# PROC099A_Tempsensor.net
KiCad netlist of a schematic drawn in Altium Designer
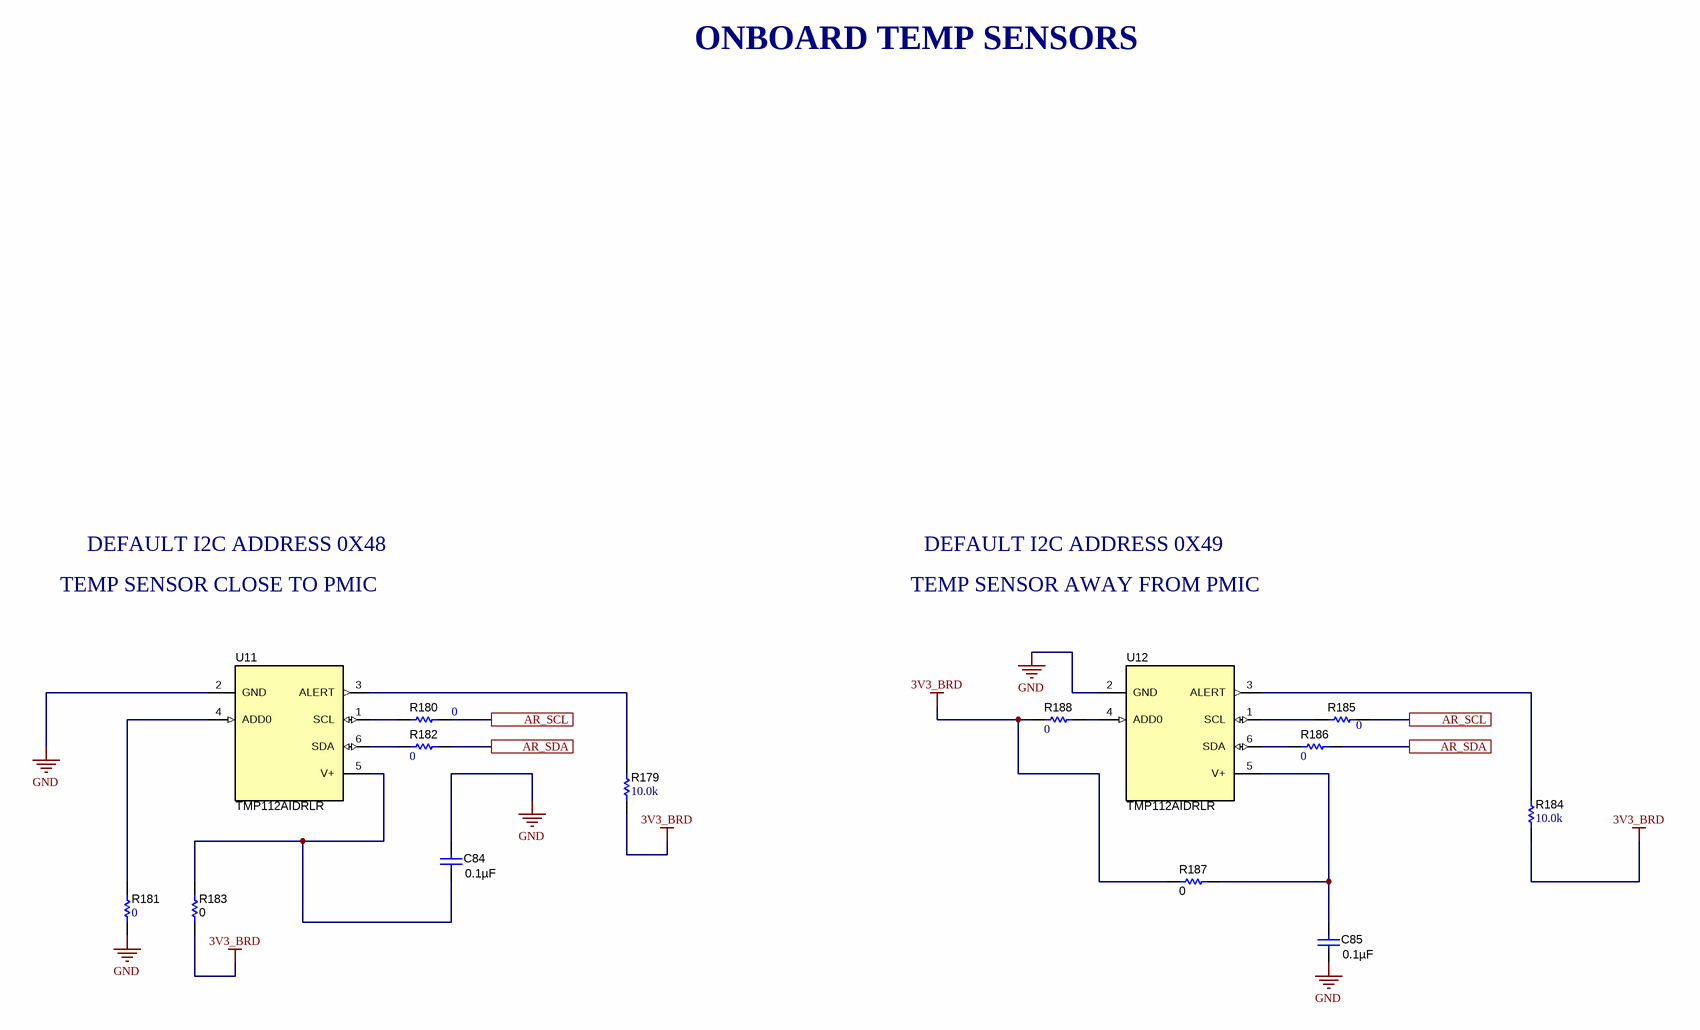
[diagram p0: PROC099A_Tempsensor.SchDoc]

(export (version "E")
  (design (tool "Eeschema 10.0.6"))
  (components
    (comp (ref "C84")
      (value "C0402C104K8RACTU")
      (footprint "0402L")
      (description "CAP, CERM, 0.1 µF, 10 V,+/- 10%, X7R, 0402")
      (fields (field (name "MANUFACTURER") "Kemet") (field (name "VALUEDISPLAYED") "0.1µF"))
      (libsource (lib "Altium Vault - TI") (part "Capacitor"))
    )
    (comp (ref "C85")
      (value "C0402C104K8RACTU")
      (footprint "0402L")
      (description "CAP, CERM, 0.1 µF, 10 V,+/- 10%, X7R, 0402")
      (fields (field (name "MANUFACTURER") "Kemet") (field (name "VALUEDISPLAYED") "0.1µF"))
      (libsource (lib "Altium Vault - TI") (part "Capacitor"))
    )
    (comp (ref "R179")
      (value "CRCW040210K0FKED")
      (footprint "0402L")
      (description "RES, 10.0 k, 1%, 0.063 W, AEC-Q200 Grade 0, 0402")
      (fields (field (name "MANUFACTURER") "Vishay-Dale") (field (name "VALUEDISPLAYED") "10.0k"))
      (libsource (lib "Altium Vault - TI") (part "Resistor"))
    )
    (comp (ref "R180")
      (value "CRCW02010000Z0ED")
      (footprint "0201_Silk")
      (description "RES, 0, 5%, 0.05 W, 0201")
      (fields (field (name "MANUFACTURER") "Vishay-Dale") (field (name "VALUEDISPLAYED") "0"))
      (libsource (lib "Altium Vault - TI") (part "Resistor"))
    )
    (comp (ref "R181")
      (value "CRCW02010000Z0ED")
      (footprint "0201_Silk")
      (description "RES, 0, 5%, 0.05 W, 0201")
      (fields (field (name "MANUFACTURER") "Vishay-Dale") (field (name "VALUEDISPLAYED") "0"))
      (libsource (lib "Altium Vault - TI") (part "Resistor"))
    )
    (comp (ref "R182")
      (value "CRCW02010000Z0ED")
      (footprint "0201_Silk")
      (description "RES, 0, 5%, 0.05 W, 0201")
      (fields (field (name "MANUFACTURER") "Vishay-Dale") (field (name "VALUEDISPLAYED") "0"))
      (libsource (lib "Altium Vault - TI") (part "Resistor"))
    )
    (comp (ref "R183")
      (value "ERJ-2GE0R00X")
      (footprint "0402L")
      (description "RES, 0, 5%, 0.063 W, 0402")
      (fields
        (field (name "MANUFACTURER") "Panasonic")
        (field (name "VALUEDISPLAYED") "0")
        (field (name "PUBLISHER") "Texas Instruments")
      )
      (libsource (lib "Altium Vault - TI") (part "Resistor"))
    )
    (comp (ref "R184")
      (value "CRCW040210K0FKED")
      (footprint "0402L")
      (description "RES, 10.0 k, 1%, 0.063 W, AEC-Q200 Grade 0, 0402")
      (fields (field (name "MANUFACTURER") "Vishay-Dale") (field (name "VALUEDISPLAYED") "10.0k"))
      (libsource (lib "Altium Vault - TI") (part "Resistor"))
    )
    (comp (ref "R185")
      (value "CRCW02010000Z0ED")
      (footprint "0201_Silk")
      (description "RES, 0, 5%, 0.05 W, 0201")
      (fields (field (name "MANUFACTURER") "Vishay-Dale") (field (name "VALUEDISPLAYED") "0"))
      (libsource (lib "Altium Vault - TI") (part "Resistor"))
    )
    (comp (ref "R186")
      (value "CRCW02010000Z0ED")
      (footprint "0201_Silk")
      (description "RES, 0, 5%, 0.05 W, 0201")
      (fields (field (name "MANUFACTURER") "Vishay-Dale") (field (name "VALUEDISPLAYED") "0"))
      (libsource (lib "Altium Vault - TI") (part "Resistor"))
    )
    (comp (ref "R187")
      (value "ERJ-2GE0R00X")
      (footprint "0402L")
      (description "RES, 0, 5%, 0.063 W, 0402")
      (fields
        (field (name "MANUFACTURER") "Panasonic")
        (field (name "VALUEDISPLAYED") "0")
        (field (name "PUBLISHER") "Texas Instruments")
      )
      (libsource (lib "Altium Vault - TI") (part "Resistor"))
    )
    (comp (ref "R188")
      (value "CRCW02010000Z0ED")
      (footprint "0201_Silk")
      (description "RES, 0, 5%, 0.05 W, 0201")
      (fields (field (name "MANUFACTURER") "Vishay-Dale") (field (name "VALUEDISPLAYED") "0"))
      (libsource (lib "Altium Vault - TI") (part "Resistor"))
    )
    (comp (ref "U11")
      (value "TMP112AIDRLR")
      (footprint "DRL0006A")
      (fields
        (field (name "ALTERNATE PARTNUMBER") "TMP112AIDRLT")
        (field (name "MANUFACTURER") "Texas Instruments")
        (field (name "PARTNUMBER") "TMP112AIDRLR")
        (field (name "PUBLISHER") "Texas Instruments")
      )
      (libsource (lib "Altium Vault - TI") (part "TMP112"))
    )
    (comp (ref "U12")
      (value "TMP112AIDRLR")
      (footprint "DRL0006A")
      (fields
        (field (name "ALTERNATE PARTNUMBER") "TMP112AIDRLT")
        (field (name "MANUFACTURER") "Texas Instruments")
        (field (name "PARTNUMBER") "TMP112AIDRLR")
        (field (name "PUBLISHER") "Texas Instruments")
      )
      (libsource (lib "Altium Vault - TI") (part "CMP-0067397-2"))
    )
  )
  (nets
    (net (code "1") (name "/AR_SCL") (class "Default")
      (node (ref "R180") (pin "1") (pinfunction "1_1") (pintype "passive"))
      (node (ref "R185") (pin "1") (pinfunction "1_1") (pintype "passive"))
    )
    (net (code "2") (name "/AR_SDA") (class "Default")
      (node (ref "R182") (pin "2") (pinfunction "2_2") (pintype "passive"))
      (node (ref "R186") (pin "2") (pinfunction "2_2") (pintype "passive"))
    )
    (net (code "3") (name "3V3_BRD") (class "Default")
      (node (ref "R179") (pin "2") (pinfunction "2_2") (pintype "passive"))
      (node (ref "R183") (pin "2") (pinfunction "2_2") (pintype "passive"))
      (node (ref "R184") (pin "2") (pinfunction "2_2") (pintype "passive"))
      (node (ref "R187") (pin "2") (pinfunction "2_2") (pintype "passive"))
      (node (ref "R188") (pin "1") (pinfunction "1_1") (pintype "passive"))
    )
    (net (code "4") (name "GND") (class "Default")
      (node (ref "C84") (pin "1") (pinfunction "1_1") (pintype "passive"))
      (node (ref "C85") (pin "2") (pinfunction "2_2") (pintype "passive"))
      (node (ref "R181") (pin "2") (pinfunction "2_2") (pintype "passive"))
      (node (ref "U11") (pin "2") (pinfunction "GND_2") (pintype "power_in"))
      (node (ref "U12") (pin "2") (pinfunction "GND_2") (pintype "power_in"))
    )
    (net (code "5") (name "Net-(U11-ADD0)") (class "Default")
      (node (ref "R181") (pin "1") (pinfunction "1_1") (pintype "passive"))
      (node (ref "U11") (pin "4") (pinfunction "ADD0_4") (pintype "input"))
    )
    (net (code "6") (name "Net-(U11-ALERT)") (class "Default")
      (node (ref "R179") (pin "1") (pinfunction "1_1") (pintype "passive"))
      (node (ref "U11") (pin "3") (pinfunction "ALERT_3") (pintype "output"))
    )
    (net (code "7") (name "Net-(U11-SCL)") (class "Default")
      (node (ref "R180") (pin "2") (pinfunction "2_2") (pintype "passive"))
      (node (ref "U11") (pin "1") (pinfunction "SCL_1") (pintype "bidirectional"))
    )
    (net (code "8") (name "Net-(U11-SDA)") (class "Default")
      (node (ref "R182") (pin "1") (pinfunction "1_1") (pintype "passive"))
      (node (ref "U11") (pin "6") (pinfunction "SDA_6") (pintype "bidirectional"))
    )
    (net (code "9") (name "Net-(U11-V+)") (class "Default")
      (node (ref "C84") (pin "2") (pinfunction "2_2") (pintype "passive"))
      (node (ref "R183") (pin "1") (pinfunction "1_1") (pintype "passive"))
      (node (ref "U11") (pin "5") (pinfunction "V+_5") (pintype "power_in"))
    )
    (net (code "10") (name "Net-(U12-ADD0)") (class "Default")
      (node (ref "R188") (pin "2") (pinfunction "2_2") (pintype "passive"))
      (node (ref "U12") (pin "4") (pinfunction "ADD0_4") (pintype "input"))
    )
    (net (code "11") (name "Net-(U12-ALERT)") (class "Default")
      (node (ref "R184") (pin "1") (pinfunction "1_1") (pintype "passive"))
      (node (ref "U12") (pin "3") (pinfunction "ALERT_3") (pintype "output"))
    )
    (net (code "12") (name "Net-(U12-SCL)") (class "Default")
      (node (ref "R185") (pin "2") (pinfunction "2_2") (pintype "passive"))
      (node (ref "U12") (pin "1") (pinfunction "SCL_1") (pintype "bidirectional"))
    )
    (net (code "13") (name "Net-(U12-SDA)") (class "Default")
      (node (ref "R186") (pin "1") (pinfunction "1_1") (pintype "passive"))
      (node (ref "U12") (pin "6") (pinfunction "SDA_6") (pintype "bidirectional"))
    )
    (net (code "14") (name "Net-(U12-V+)") (class "Default")
      (node (ref "C85") (pin "1") (pinfunction "1_1") (pintype "passive"))
      (node (ref "R187") (pin "1") (pinfunction "1_1") (pintype "passive"))
      (node (ref "U12") (pin "5") (pinfunction "V+_5") (pintype "power_in"))
    )
  )
)
